# HallConnector.net
KiCad netlist of a schematic drawn in Altium Designer
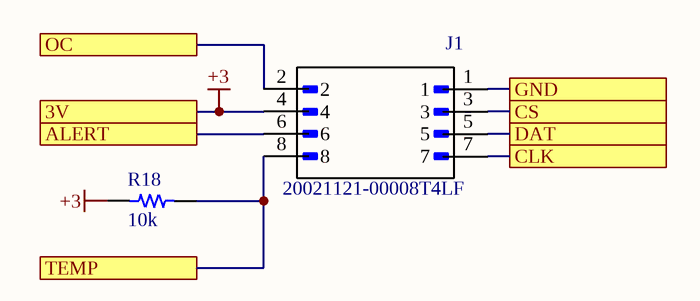
[diagram p0: HallConnector.SchDoc]

(export (version "E")
  (design (tool "Eeschema 10.0.6"))
  (components
    (comp (ref "J1")
      (value "20021121-00008T4LF")
      (footprint "*AMPHENOL_20021121-00008T4LF")
      (libsource (lib "Schlib2") (part "20021121-00008T4LF"))
    )
    (comp (ref "R18")
      (value "10k")
      (footprint "RES 0402_1005")
      (description "RES 249K OHM 0.1% 1/10W 0402")
      (fields
        (field (name "PART NUMBER") "RP73PF1E249KBTD")
        (field (name "MANUFACTURER") "TE Connectivity Passive Product")
      )
      (libsource (lib "Celestial Altium Library - altium_library") (part "Resistor"))
    )
  )
  (nets
    (net (code "1") (name "+3") (class "Default")
      (node (ref "J1") (pin "4") (pinfunction "4_4") (pintype "passive"))
      (node (ref "R18") (pin "1") (pinfunction "1_1") (pintype "passive"))
    )
    (net (code "2") (name "/ALERT") (class "Default")
      (node (ref "J1") (pin "6") (pinfunction "6_6") (pintype "passive"))
    )
    (net (code "3") (name "/CLK") (class "Default")
      (node (ref "J1") (pin "7") (pinfunction "7_7") (pintype "passive"))
    )
    (net (code "4") (name "/CS") (class "Default")
      (node (ref "J1") (pin "3") (pinfunction "3_3") (pintype "passive"))
    )
    (net (code "5") (name "/DAT") (class "Default")
      (node (ref "J1") (pin "5") (pinfunction "5_5") (pintype "passive"))
    )
    (net (code "6") (name "/GND") (class "Default")
      (node (ref "J1") (pin "1") (pinfunction "1_1") (pintype "passive"))
    )
    (net (code "7") (name "/OC") (class "Default")
      (node (ref "J1") (pin "2") (pinfunction "2_2") (pintype "passive"))
    )
    (net (code "8") (name "/TEMP") (class "Default")
      (node (ref "J1") (pin "8") (pinfunction "8_8") (pintype "passive"))
      (node (ref "R18") (pin "2") (pinfunction "2_2") (pintype "passive"))
    )
  )
)
